# ACS72x-Breakout_v11.net
KiCad netlist of a schematic drawn in EAGLE
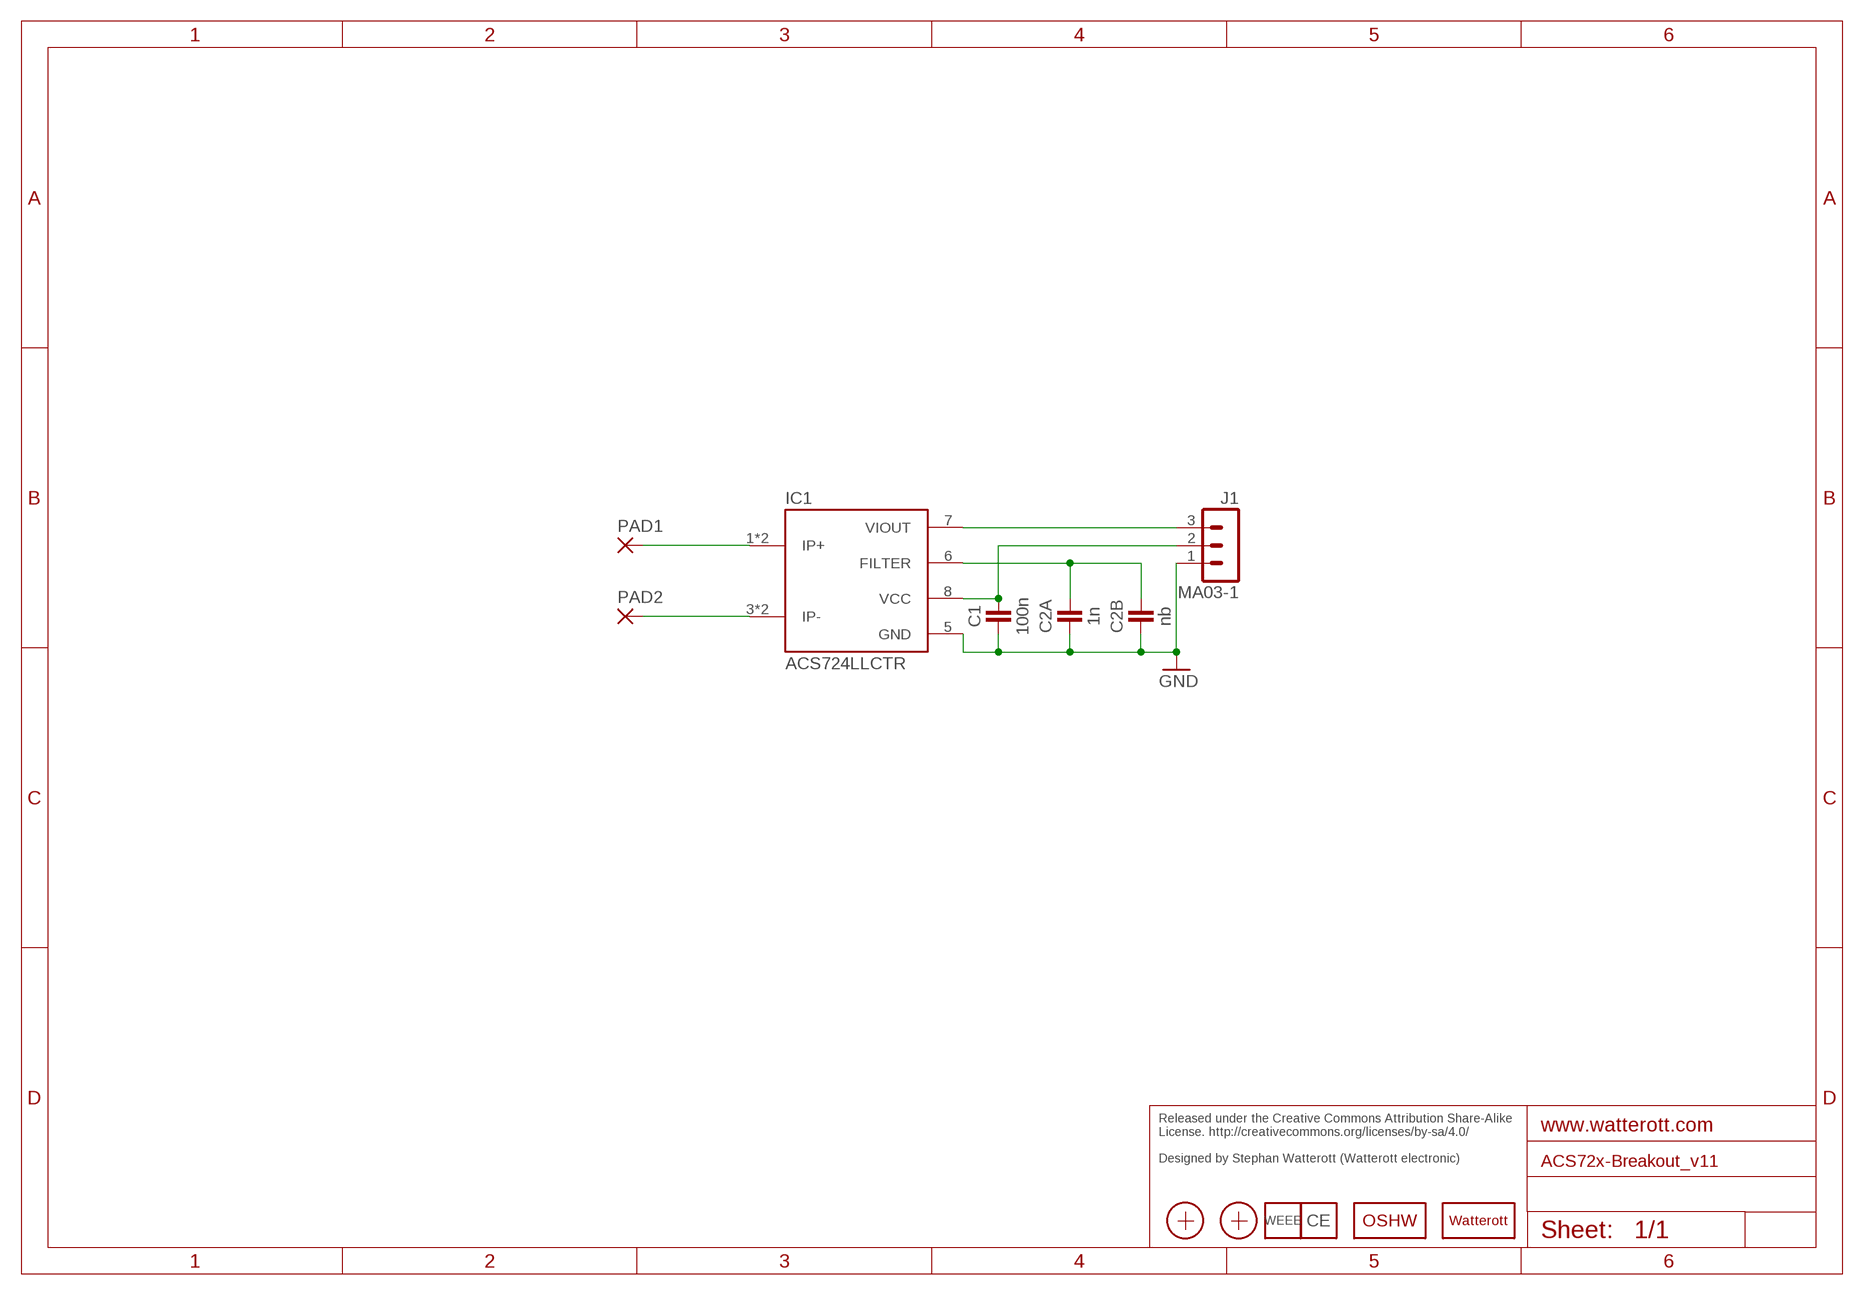
[diagram p0: schematic, sheet 1]

(export (version "E")
  (design (tool "Eeschema 10.0.6"))
  (components
    (comp (ref "C1")
      (value "100n")
      (footprint "eagle-import:C0402")
      (libsource (lib "eagle-import") (part "CAPACITOR-0402"))
    )
    (comp (ref "C2A")
      (value "1n")
      (footprint "eagle-import:C0402")
      (libsource (lib "eagle-import") (part "CAPACITOR-0402"))
    )
    (comp (ref "C2B")
      (value "nb")
      (footprint "eagle-import:C0603")
      (libsource (lib "eagle-import") (part "CAPACITOR-0603"))
    )
    (comp (ref "IC1")
      (value "ACS724LLCTR")
      (footprint "eagle-import:SO8")
      (libsource (lib "eagle-import") (part "ACS724LLCTR"))
    )
    (comp (ref "J1")
      (value "MA03-1")
      (footprint "eagle-import:MA03-1")
      (libsource (lib "eagle-import") (part "MA03-1"))
    )
    (comp (ref "LOGO1")
      (value "LOGO_CE-2")
      (footprint "eagle-import:CE_2MM")
      (libsource (lib "eagle-import") (part "LOGO_CE-2"))
    )
    (comp (ref "LOGO2")
      (value "OSHW_LOGOX0070")
      (footprint "eagle-import:OSHW_6X70")
      (libsource (lib "eagle-import") (part "OSHW_LOGOX0070"))
    )
    (comp (ref "LOGO3")
      (value "LOGO-S_PLACE_S")
      (footprint "eagle-import:SPARK_TPLACE_S")
      (libsource (lib "eagle-import") (part "LOGO-S_PLACE_S"))
    )
    (comp (ref "LOGO4")
      (value "LOGO_WEEE-4")
      (footprint "eagle-import:WEEE_4MM")
      (libsource (lib "eagle-import") (part "LOGO_WEEE-4"))
    )
    (comp (ref "PAD1")
      (value "WIREPADSMD5-2,5")
      (footprint "eagle-import:5-2,5")
      (libsource (lib "eagle-import") (part "WIREPADSMD5-2,5"))
    )
    (comp (ref "PAD2")
      (value "WIREPADSMD5-2,5")
      (footprint "eagle-import:5-2,5")
      (libsource (lib "eagle-import") (part "WIREPADSMD5-2,5"))
    )
    (comp (ref "X1")
      (value "PASSER-07")
      (footprint "eagle-import:PASSER_07MM")
      (libsource (lib "eagle-import") (part "PASSER-07"))
    )
    (comp (ref "X2")
      (value "PASSER-07")
      (footprint "eagle-import:PASSER_07MM")
      (libsource (lib "eagle-import") (part "PASSER-07"))
    )
  )
  (nets
    (net (code "1") (name "GND") (class "Default")
      (node (ref "C1") (pin "1") (pinfunction "1_1") (pintype "passive"))
      (node (ref "C2A") (pin "1") (pinfunction "1_1") (pintype "passive"))
      (node (ref "C2B") (pin "1") (pinfunction "1_1") (pintype "passive"))
      (node (ref "IC1") (pin "5") (pinfunction "GND_5") (pintype "power_in"))
      (node (ref "J1") (pin "1") (pinfunction "1_1") (pintype "passive"))
    )
    (net (code "2") (name "Net-(IC1-FILTER)") (class "Default")
      (node (ref "C2A") (pin "2") (pinfunction "2_2") (pintype "passive"))
      (node (ref "C2B") (pin "2") (pinfunction "2_2") (pintype "passive"))
      (node (ref "IC1") (pin "6") (pinfunction "FILTER_6") (pintype "output"))
    )
    (net (code "3") (name "Net-(IC1-VCC)") (class "Default")
      (node (ref "C1") (pin "2") (pinfunction "2_2") (pintype "passive"))
      (node (ref "IC1") (pin "8") (pinfunction "VCC_8") (pintype "power_in"))
      (node (ref "J1") (pin "2") (pinfunction "2_2") (pintype "passive"))
    )
    (net (code "4") (name "Net-(IC1-VIOUT)") (class "Default")
      (node (ref "IC1") (pin "7") (pinfunction "VIOUT_7") (pintype "output"))
      (node (ref "J1") (pin "3") (pinfunction "3_3") (pintype "passive"))
    )
    (net (code "5") (name "Net-(PAD1-P)") (class "Default")
      (node (ref "IC1") (pin "1") (pinfunction "IP+_1") (pintype "passive"))
      (node (ref "IC1") (pin "2") (pinfunction "IP+_2") (pintype "passive"))
      (node (ref "PAD1") (pin "1") (pinfunction "P_1") (pintype "passive"))
    )
    (net (code "6") (name "Net-(PAD2-P)") (class "Default")
      (node (ref "IC1") (pin "3") (pinfunction "IP-_3") (pintype "passive"))
      (node (ref "IC1") (pin "4") (pinfunction "IP-_4") (pintype "passive"))
      (node (ref "PAD2") (pin "1") (pinfunction "P_1") (pintype "passive"))
    )
  )
)
